# OpenBook_Schematic.net
KiCad netlist of a schematic drawn in EAGLE
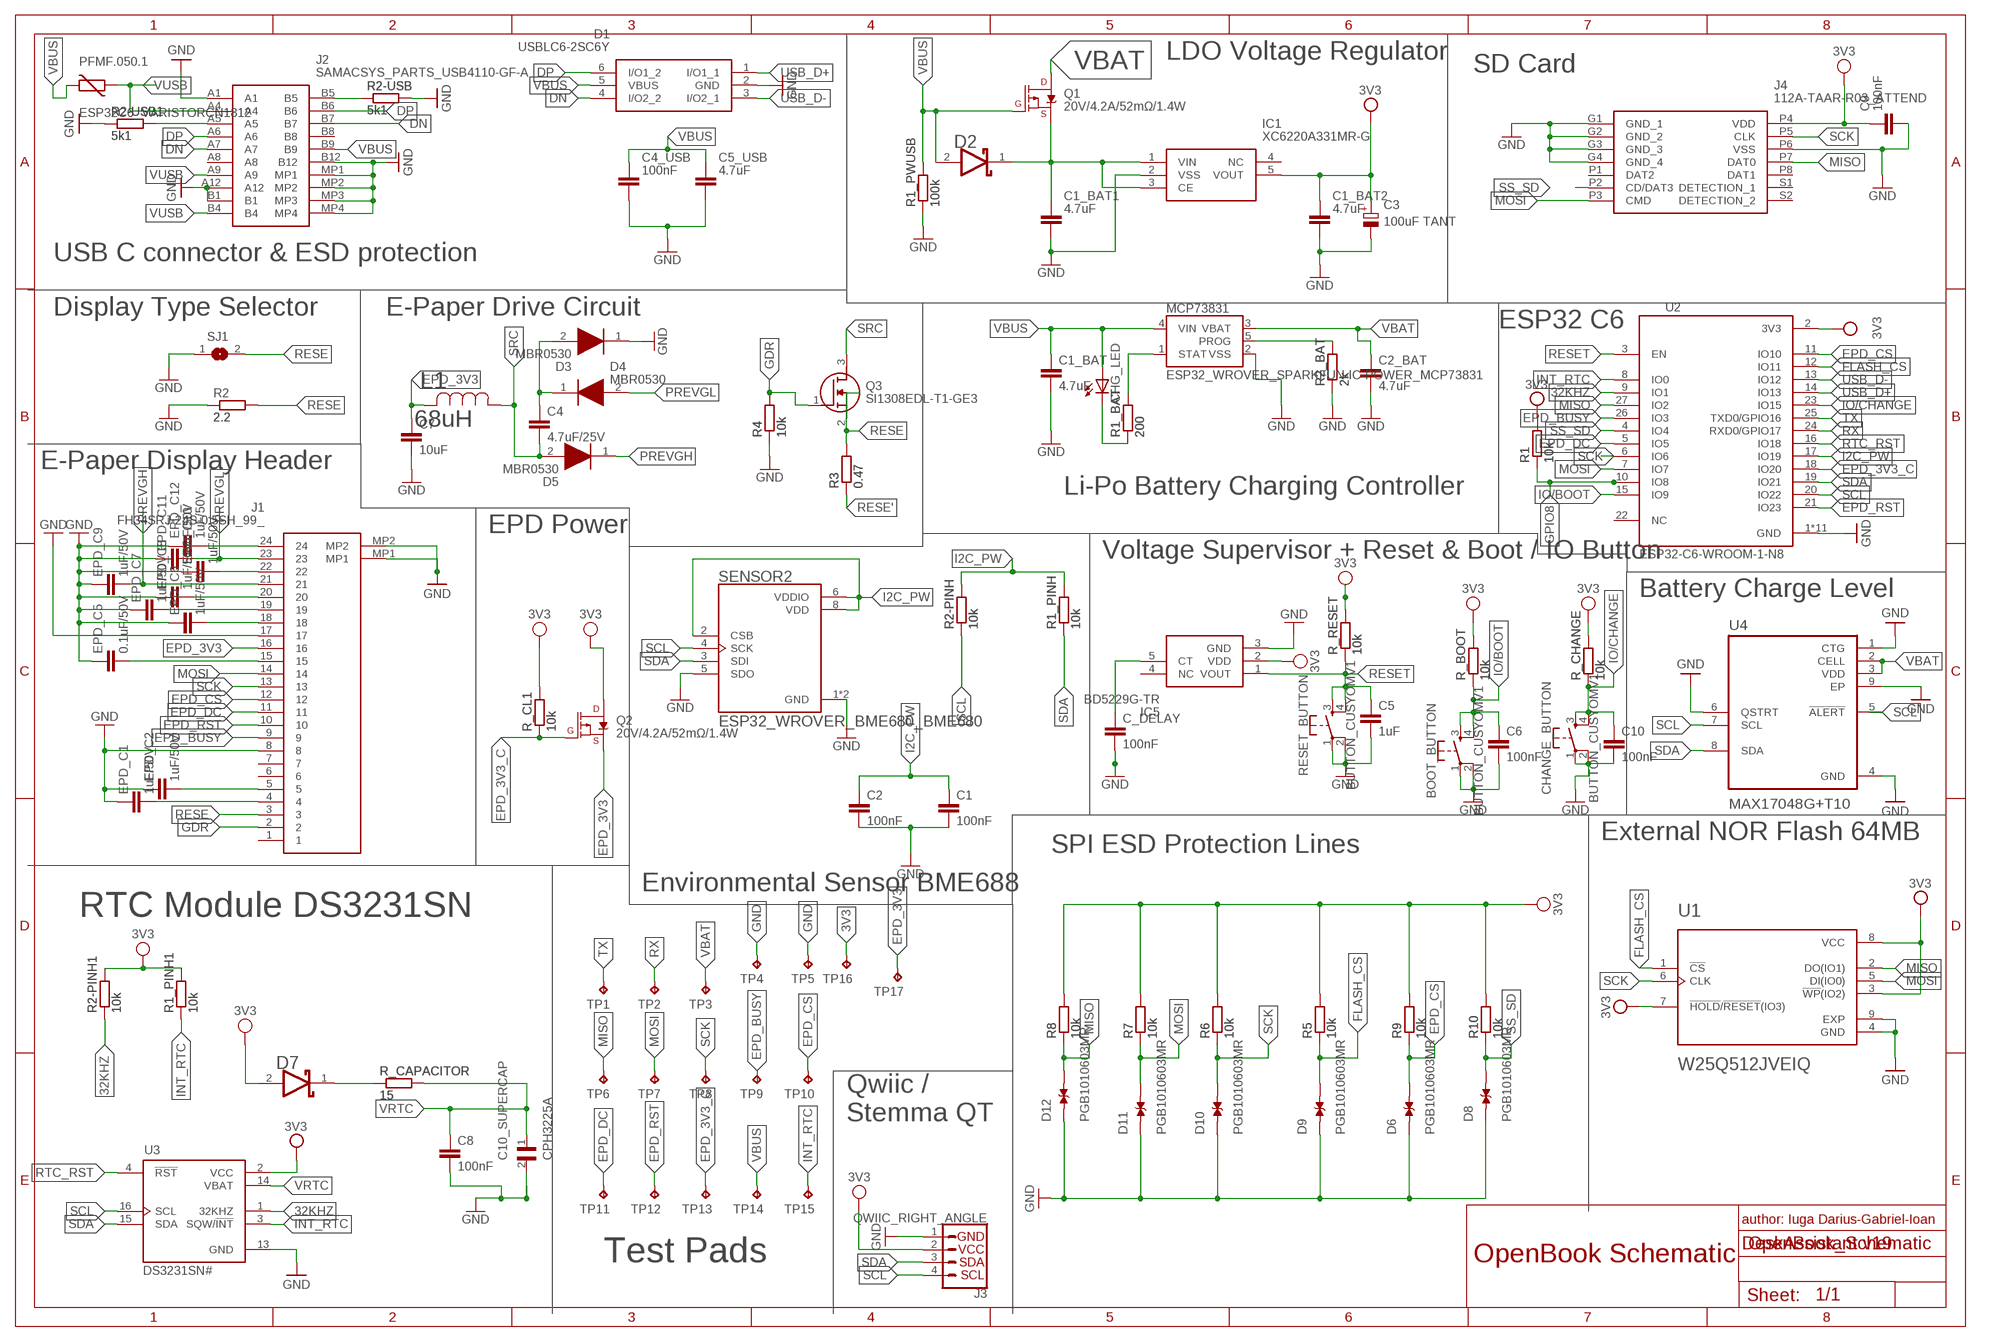
[diagram p0: schematic, sheet 1]

(export (version "E")
  (design (tool "Eeschema 10.0.6"))
  (components
    (comp (ref "BOOT_BUTTON")
      (value "BUTTON_CUSYOMV1")
      (footprint "eagle-import:MYBUTTON")
      (libsource (lib "eagle-import") (part "BUTTON_CUSYOMV1"))
    )
    (comp (ref "C1")
      (value "100nF")
      (footprint "eagle-import:ESP32_WROVER_EAGLE-LTSPICE_C0402")
      (libsource (lib "eagle-import") (part "ESP32_WROVER_EAGLE-LTSPICE_CC0402"))
    )
    (comp (ref "C1_BAT")
      (value "4.7uF")
      (footprint "eagle-import:ESP32_WROVER_EAGLE-LTSPICE_C0402")
      (libsource (lib "eagle-import") (part "ESP32_WROVER_EAGLE-LTSPICE_CC0402"))
    )
    (comp (ref "C1_BAT1")
      (value "4.7uF")
      (footprint "eagle-import:CAPC1005X60")
      (libsource (lib "eagle-import") (part "CCHIP-0402(1005-METRIC)_"))
    )
    (comp (ref "C1_BAT2")
      (value "4.7uF")
      (footprint "eagle-import:CAPM3216X180")
      (libsource (lib "eagle-import") (part "CTANTALUM-1206(3216-METRIC)_"))
    )
    (comp (ref "C2")
      (value "100nF")
      (footprint "eagle-import:ESP32_WROVER_EAGLE-LTSPICE_C0402")
      (libsource (lib "eagle-import") (part "ESP32_WROVER_EAGLE-LTSPICE_CC0402"))
    )
    (comp (ref "C2_BAT")
      (value "4.7uF")
      (footprint "eagle-import:ESP32_WROVER_EAGLE-LTSPICE_C0402")
      (libsource (lib "eagle-import") (part "ESP32_WROVER_EAGLE-LTSPICE_CC0402"))
    )
    (comp (ref "C3")
      (value "100uF TANT")
      (footprint "eagle-import:CAPMP3216X180N")
      (libsource (lib "eagle-import") (part "C-POLTANTALUM-1206(3216-METRIC)_"))
    )
    (comp (ref "C4")
      (value "4.7uF/25V")
      (footprint "eagle-import:EAGLE-LTSPICE_C0402")
      (libsource (lib "eagle-import") (part "EAGLE-LTSPICE_CC0402"))
    )
    (comp (ref "C4_USB")
      (value "100nF")
      (footprint "eagle-import:CAPC1005X60")
      (libsource (lib "eagle-import") (part "CCHIP-0402(1005-METRIC)_"))
    )
    (comp (ref "C5")
      (value "1uF")
      (footprint "eagle-import:ESP32_WROVER_EAGLE-LTSPICE_C0402")
      (libsource (lib "eagle-import") (part "ESP32_WROVER_EAGLE-LTSPICE_CC0402"))
    )
    (comp (ref "C5_USB")
      (value "4.7uF")
      (footprint "eagle-import:CAPC1005X60")
      (libsource (lib "eagle-import") (part "CCHIP-0402(1005-METRIC)_"))
    )
    (comp (ref "C6")
      (value "100nF")
      (footprint "eagle-import:ESP32_WROVER_EAGLE-LTSPICE_C0402")
      (libsource (lib "eagle-import") (part "ESP32_WROVER_EAGLE-LTSPICE_CC0402"))
    )
    (comp (ref "C7")
      (value "10uF")
      (footprint "eagle-import:EAGLE-LTSPICE_C0402")
      (libsource (lib "eagle-import") (part "EAGLE-LTSPICE_CC0402"))
    )
    (comp (ref "C8")
      (value "100nF")
      (footprint "eagle-import:EAGLE-LTSPICE_C0402")
      (libsource (lib "eagle-import") (part "EAGLE-LTSPICE_CC0402"))
    )
    (comp (ref "C9")
      (value "100nF")
      (footprint "eagle-import:CAPC1005X60")
      (libsource (lib "eagle-import") (part "CCHIP-0402(1005-METRIC)_"))
    )
    (comp (ref "C10")
      (value "100nF")
      (footprint "eagle-import:ESP32_WROVER_EAGLE-LTSPICE_C0402")
      (libsource (lib "eagle-import") (part "ESP32_WROVER_EAGLE-LTSPICE_CC0402"))
    )
    (comp (ref "C10_SUPERCAP")
      (value "CPH3225A")
      (footprint "eagle-import:CAPCP3225X100N")
      (fields (field (name "MF") "Seiko Instruments"))
      (libsource (lib "eagle-import") (part "CPH3225A"))
    )
    (comp (ref "CHANGE_BUTTON")
      (value "BUTTON_CUSYOMV1")
      (footprint "eagle-import:MYBUTTON")
      (libsource (lib "eagle-import") (part "BUTTON_CUSYOMV1"))
    )
    (comp (ref "CHG_LED")
      (value "ADAFRUIT_LEDCHIP-LED0603")
      (footprint "eagle-import:ADAFRUIT_CHIP-LED0603")
      (libsource (lib "eagle-import") (part "ADAFRUIT_LEDCHIP-LED0603"))
    )
    (comp (ref "C_DELAY")
      (value "100nF")
      (footprint "eagle-import:ESP32_WROVER_EAGLE-LTSPICE_C0402")
      (libsource (lib "eagle-import") (part "ESP32_WROVER_EAGLE-LTSPICE_CC0402"))
    )
    (comp (ref "D1")
      (value "USBLC6-2SC6Y")
      (footprint "eagle-import:SOT95P280X145-6N")
      (fields (field (name "MF") "STMicroelectronics"))
      (libsource (lib "eagle-import") (part "USBLC6-2SC6Y"))
    )
    (comp (ref "D2")
      (value "ESP32_WROVER_AVX---SD0805S020S1R0_AVX_SD0805S020S1R0_0_0AVX_SD0805S020S1R0_0_0")
      (footprint "eagle-import:ESP32_WROVER_AVX---SD0805S020S1R0_AVX_SD0805S020S1R0_0")
      (fields
        (field (name "DIGIKEY_PART_NUMBER") "478-7800-1-ND")
        (field (name "MF") "AVX")
        (field (name "MOUSER_PART_NUMBER") "581-SD0805S020S1R0")
      )
      (libsource (lib "eagle-import") (part "ESP32_WROVER_AVX---SD0805S020S1R0_AVX_SD0805S020S1R0_0_0AVX_SD0805S020S1R0_0_0"))
    )
    (comp (ref "D3")
      (value "MBR0530")
      (footprint "eagle-import:SOD3716X135N")
      (fields (field (name "MF") "ON Semiconductor"))
      (libsource (lib "eagle-import") (part "MBR0530"))
    )
    (comp (ref "D4")
      (value "MBR0530")
      (footprint "eagle-import:SOD3716X135N")
      (fields (field (name "MF") "ON Semiconductor"))
      (libsource (lib "eagle-import") (part "MBR0530"))
    )
    (comp (ref "D5")
      (value "MBR0530")
      (footprint "eagle-import:SOD3716X135N")
      (fields (field (name "MF") "ON Semiconductor"))
      (libsource (lib "eagle-import") (part "MBR0530"))
    )
    (comp (ref "D6")
      (value "PGB1010603MR")
      (footprint "eagle-import:DIOC1608X36N")
      (fields (field (name "MF") "Littelfuse Inc."))
      (libsource (lib "eagle-import") (part "PGB1010603MR"))
    )
    (comp (ref "D7")
      (value "ESP32_WROVER_AVX---SD0805S020S1R0_AVX_SD0805S020S1R0_0_0AVX_SD0805S020S1R0_0_0")
      (footprint "eagle-import:ESP32_WROVER_AVX---SD0805S020S1R0_AVX_SD0805S020S1R0_0")
      (fields
        (field (name "DIGIKEY_PART_NUMBER") "478-7800-1-ND")
        (field (name "MF") "AVX")
        (field (name "MOUSER_PART_NUMBER") "581-SD0805S020S1R0")
      )
      (libsource (lib "eagle-import") (part "ESP32_WROVER_AVX---SD0805S020S1R0_AVX_SD0805S020S1R0_0_0AVX_SD0805S020S1R0_0_0"))
    )
    (comp (ref "D8")
      (value "PGB1010603MR")
      (footprint "eagle-import:DIOC1608X36N")
      (fields (field (name "MF") "Littelfuse Inc."))
      (libsource (lib "eagle-import") (part "PGB1010603MR"))
    )
    (comp (ref "D9")
      (value "PGB1010603MR")
      (footprint "eagle-import:DIOC1608X36N")
      (fields (field (name "MF") "Littelfuse Inc."))
      (libsource (lib "eagle-import") (part "PGB1010603MR"))
    )
    (comp (ref "D10")
      (value "PGB1010603MR")
      (footprint "eagle-import:DIOC1608X36N")
      (fields (field (name "MF") "Littelfuse Inc."))
      (libsource (lib "eagle-import") (part "PGB1010603MR"))
    )
    (comp (ref "D11")
      (value "PGB1010603MR")
      (footprint "eagle-import:DIOC1608X36N")
      (fields (field (name "MF") "Littelfuse Inc."))
      (libsource (lib "eagle-import") (part "PGB1010603MR"))
    )
    (comp (ref "D12")
      (value "PGB1010603MR")
      (footprint "eagle-import:DIOC1608X36N")
      (fields (field (name "MF") "Littelfuse Inc."))
      (libsource (lib "eagle-import") (part "PGB1010603MR"))
    )
    (comp (ref "EPD_C1")
      (value "1uF/50V")
      (footprint "eagle-import:ESP32_WROVER_EAGLE-LTSPICE_C0402")
      (libsource (lib "eagle-import") (part "ESP32_WROVER_EAGLE-LTSPICE_CC0402"))
    )
    (comp (ref "EPD_C2")
      (value "1uF/50V")
      (footprint "eagle-import:ESP32_WROVER_EAGLE-LTSPICE_C0402")
      (libsource (lib "eagle-import") (part "ESP32_WROVER_EAGLE-LTSPICE_CC0402"))
    )
    (comp (ref "EPD_C5")
      (value "0.1uF/50V")
      (footprint "eagle-import:ESP32_WROVER_EAGLE-LTSPICE_C0402")
      (libsource (lib "eagle-import") (part "ESP32_WROVER_EAGLE-LTSPICE_CC0402"))
    )
    (comp (ref "EPD_C6")
      (value "1uF/50V")
      (footprint "eagle-import:ESP32_WROVER_EAGLE-LTSPICE_C0402")
      (libsource (lib "eagle-import") (part "ESP32_WROVER_EAGLE-LTSPICE_CC0402"))
    )
    (comp (ref "EPD_C7")
      (value "1uF/50V")
      (footprint "eagle-import:ESP32_WROVER_EAGLE-LTSPICE_C0402")
      (libsource (lib "eagle-import") (part "ESP32_WROVER_EAGLE-LTSPICE_CC0402"))
    )
    (comp (ref "EPD_C8")
      (value "1uF/50V")
      (footprint "eagle-import:ESP32_WROVER_EAGLE-LTSPICE_C0402")
      (libsource (lib "eagle-import") (part "ESP32_WROVER_EAGLE-LTSPICE_CC0402"))
    )
    (comp (ref "EPD_C9")
      (value "1uF/50V")
      (footprint "eagle-import:ESP32_WROVER_EAGLE-LTSPICE_C0402")
      (libsource (lib "eagle-import") (part "ESP32_WROVER_EAGLE-LTSPICE_CC0402"))
    )
    (comp (ref "EPD_C10")
      (value "1uF/50V")
      (footprint "eagle-import:ESP32_WROVER_EAGLE-LTSPICE_C0402")
      (libsource (lib "eagle-import") (part "ESP32_WROVER_EAGLE-LTSPICE_CC0402"))
    )
    (comp (ref "EPD_C11")
      (value "1uF/50V")
      (footprint "eagle-import:ESP32_WROVER_EAGLE-LTSPICE_C0402")
      (libsource (lib "eagle-import") (part "ESP32_WROVER_EAGLE-LTSPICE_CC0402"))
    )
    (comp (ref "EPD_C12")
      (value "1uF/50V")
      (footprint "eagle-import:ESP32_WROVER_EAGLE-LTSPICE_C0402")
      (libsource (lib "eagle-import") (part "ESP32_WROVER_EAGLE-LTSPICE_CC0402"))
    )
    (comp (ref "IC1")
      (value "XC6220A331MR-G")
      (footprint "eagle-import:SOT95P280X120-5N")
      (fields (field (name "MOUSER_PART_NUMBER") "865-XC6220A331MR-G"))
      (libsource (lib "eagle-import") (part "XC6220A331MR-G"))
    )
    (comp (ref "IC5")
      (value "BD5229G-TR")
      (footprint "eagle-import:SOT95P280X125-5N")
      (fields (field (name "MOUSER_PART_NUMBER") "755-BD5229G-TR"))
      (libsource (lib "eagle-import") (part "BD5229G-TR"))
    )
    (comp (ref "J1")
      (value "FH34SRJ-24S-0.5SH_99_")
      (footprint "eagle-import:FH34SRJ24S05SH99")
      (fields
        (field (name "MANUFACTURER_PART_NUMBER") "FH34SRJ-24S-0.5SH(99)")
        (field (name "MOUSER_PART_NUMBER") "798-FH34SRJ24S05SH99")
      )
      (libsource (lib "eagle-import") (part "FH34SRJ-24S-0.5SH_99_"))
    )
    (comp (ref "J2")
      (value "SAMACSYS_PARTS_USB4110-GF-A")
      (footprint "eagle-import:SAMACSYS_PARTS_USB4110GFA")
      (fields
        (field (name "MANUFACTURER_PART_NUMBER") "USB4110-GF-A")
        (field (name "MOUSER_PART_NUMBER") "640-USB4110-GF-A")
      )
      (libsource (lib "eagle-import") (part "SAMACSYS_PARTS_USB4110-GF-A"))
    )
    (comp (ref "J3")
      (value "QWIIC_RIGHT_ANGLE")
      (footprint "eagle-import:JST04_1MM_RA")
      (libsource (lib "eagle-import") (part "QWIIC_CONNECTORJS-1MM"))
    )
    (comp (ref "J4")
      (value "112A-TAAR-R03_ATTEND")
      (footprint "eagle-import:112ATAARR03ATTEND")
      (fields (field (name "MANUFACTURER_PART_NUMBER") "112A-TAAR-R03 ATTEND"))
      (libsource (lib "eagle-import") (part "112A-TAAR-R03_ATTEND"))
    )
    (comp (ref "L1")
      (value "68uH")
      (footprint "eagle-import:IND_4828-WE-TPC_WRE")
      (fields
        (field (name "MANUFACTURER_PART_NUMBER") "744043680")
        (field (name "COPYRIGHT") "Copyright (C) 2024 Ultra Librarian. All rights reserved.")
      )
      (libsource (lib "eagle-import") (part "744043680IND_4828-WE-TPC_WRE"))
    )
    (comp (ref "MCP73831")
      (value "ESP32_WROVER_SPARKFUN-IC-POWER_MCP73831")
      (footprint "eagle-import:ESP32_WROVER_SPARKFUN-IC-POWER_SOT23-5")
      (libsource (lib "eagle-import") (part "ESP32_WROVER_SPARKFUN-IC-POWER_MCP73831"))
    )
    (comp (ref "PFMF.050.1")
      (value "ESP32C6_VARISTORCN1812")
      (footprint "eagle-import:ESP32C6_VARISTOR_CT_CN1812")
      (libsource (lib "eagle-import") (part "ESP32C6_VARISTORCN1812"))
    )
    (comp (ref "Q1")
      (value "20V/4.2A/52mΩ/1.4W")
      (footprint "eagle-import:ESP32_WROVER_SPARKFUN-DISCRETESEMI_SOT23-3")
      (libsource (lib "eagle-import") (part "ESP32_WROVER_SPARKFUN-DISCRETESEMI_MOSFET_PCH-DMG2305UX-7"))
    )
    (comp (ref "Q2")
      (value "20V/4.2A/52mΩ/1.4W")
      (footprint "eagle-import:ESP32_WROVER_SPARKFUN-DISCRETESEMI_SOT23-3")
      (libsource (lib "eagle-import") (part "ESP32_WROVER_SPARKFUN-DISCRETESEMI_MOSFET_PCH-DMG2305UX-7"))
    )
    (comp (ref "Q3")
      (value "SI1308EDL-T1-GE3")
      (footprint "eagle-import:SOT65P210X110-3N")
      (fields
        (field (name "MANUFACTURER_PART_NUMBER") "Si1308EDL-T1-GE3")
        (field (name "MOUSER_PART_NUMBER") "78-SI1308EDL-T1-GE3")
      )
      (libsource (lib "eagle-import") (part "SI1308EDL-T1-GE3"))
    )
    (comp (ref "R1")
      (value "10k")
      (footprint "eagle-import:ESP32_WROVER_EAGLE-LTSPICE_R0402")
      (libsource (lib "eagle-import") (part "ESP32_WROVER_EAGLE-LTSPICE_RR0402"))
    )
    (comp (ref "R1_BAT")
      (value "200")
      (footprint "eagle-import:ESP32_WROVER_EAGLE-LTSPICE_R0402")
      (libsource (lib "eagle-import") (part "ESP32_WROVER_EAGLE-LTSPICE_RR0402"))
    )
    (comp (ref "R1_PINH")
      (value "10k")
      (footprint "eagle-import:ESP32_WROVER_EAGLE-LTSPICE_R0402")
      (libsource (lib "eagle-import") (part "ESP32_WROVER_EAGLE-LTSPICE_RR0402"))
    )
    (comp (ref "R1_PINH1")
      (value "10k")
      (footprint "eagle-import:ESP32_WROVER_EAGLE-LTSPICE_R0402")
      (libsource (lib "eagle-import") (part "ESP32_WROVER_EAGLE-LTSPICE_RR0402"))
    )
    (comp (ref "R1_PWUSB")
      (value "100k")
      (footprint "eagle-import:ESP32_WROVER_EAGLE-LTSPICE_R0402")
      (libsource (lib "eagle-import") (part "ESP32_WROVER_EAGLE-LTSPICE_RR0402"))
    )
    (comp (ref "R2")
      (value "2.2")
      (footprint "eagle-import:ESP32_WROVER_EAGLE-LTSPICE_R0402")
      (libsource (lib "eagle-import") (part "ESP32_WROVER_EAGLE-LTSPICE_RR0402"))
    )
    (comp (ref "R2-PINH")
      (value "10k")
      (footprint "eagle-import:ESP32_WROVER_EAGLE-LTSPICE_R0402")
      (libsource (lib "eagle-import") (part "ESP32_WROVER_EAGLE-LTSPICE_RR0402"))
    )
    (comp (ref "R2-PINH1")
      (value "10k")
      (footprint "eagle-import:ESP32_WROVER_EAGLE-LTSPICE_R0402")
      (libsource (lib "eagle-import") (part "ESP32_WROVER_EAGLE-LTSPICE_RR0402"))
    )
    (comp (ref "R2-USB")
      (value "5k1")
      (footprint "eagle-import:ESP32_WROVER_EAGLE-LTSPICE_R0402")
      (libsource (lib "eagle-import") (part "ESP32_WROVER_EAGLE-LTSPICE_RR0402"))
    )
    (comp (ref "R2-USB1")
      (value "5k1")
      (footprint "eagle-import:ESP32_WROVER_EAGLE-LTSPICE_R0402")
      (libsource (lib "eagle-import") (part "ESP32_WROVER_EAGLE-LTSPICE_RR0402"))
    )
    (comp (ref "R2_BAT")
      (value "2k")
      (footprint "eagle-import:ESP32_WROVER_EAGLE-LTSPICE_R0402")
      (libsource (lib "eagle-import") (part "ESP32_WROVER_EAGLE-LTSPICE_RR0402"))
    )
    (comp (ref "R3")
      (value "0.47")
      (footprint "eagle-import:ESP32_WROVER_EAGLE-LTSPICE_R0402")
      (libsource (lib "eagle-import") (part "ESP32_WROVER_EAGLE-LTSPICE_RR0402"))
    )
    (comp (ref "R4")
      (value "10k")
      (footprint "eagle-import:ESP32_WROVER_EAGLE-LTSPICE_R0402")
      (libsource (lib "eagle-import") (part "ESP32_WROVER_EAGLE-LTSPICE_RR0402"))
    )
    (comp (ref "R5")
      (value "10k")
      (footprint "eagle-import:ESP32_WROVER_EAGLE-LTSPICE_R0402")
      (libsource (lib "eagle-import") (part "ESP32_WROVER_EAGLE-LTSPICE_RR0402"))
    )
    (comp (ref "R6")
      (value "10k")
      (footprint "eagle-import:ESP32_WROVER_EAGLE-LTSPICE_R0402")
      (libsource (lib "eagle-import") (part "ESP32_WROVER_EAGLE-LTSPICE_RR0402"))
    )
    (comp (ref "R7")
      (value "10k")
      (footprint "eagle-import:ESP32_WROVER_EAGLE-LTSPICE_R0402")
      (libsource (lib "eagle-import") (part "ESP32_WROVER_EAGLE-LTSPICE_RR0402"))
    )
    (comp (ref "R8")
      (value "10k")
      (footprint "eagle-import:ESP32_WROVER_EAGLE-LTSPICE_R0402")
      (libsource (lib "eagle-import") (part "ESP32_WROVER_EAGLE-LTSPICE_RR0402"))
    )
    (comp (ref "R9")
      (value "10k")
      (footprint "eagle-import:ESP32_WROVER_EAGLE-LTSPICE_R0402")
      (libsource (lib "eagle-import") (part "ESP32_WROVER_EAGLE-LTSPICE_RR0402"))
    )
    (comp (ref "R10")
      (value "10k")
      (footprint "eagle-import:ESP32_WROVER_EAGLE-LTSPICE_R0402")
      (libsource (lib "eagle-import") (part "ESP32_WROVER_EAGLE-LTSPICE_RR0402"))
    )
    (comp (ref "RESET_BUTTON")
      (value "BUTTON_CUSYOMV1")
      (footprint "eagle-import:MYBUTTON")
      (libsource (lib "eagle-import") (part "BUTTON_CUSYOMV1"))
    )
    (comp (ref "R_BOOT")
      (value "10k")
      (footprint "eagle-import:ESP32_WROVER_EAGLE-LTSPICE_R0402")
      (libsource (lib "eagle-import") (part "ESP32_WROVER_EAGLE-LTSPICE_RR0402"))
    )
    (comp (ref "R_CAPACITOR")
      (value "15")
      (footprint "eagle-import:ESP32_WROVER_EAGLE-LTSPICE_R0402")
      (libsource (lib "eagle-import") (part "ESP32_WROVER_EAGLE-LTSPICE_RR0402"))
    )
    (comp (ref "R_CHANGE")
      (value "10k")
      (footprint "eagle-import:ESP32_WROVER_EAGLE-LTSPICE_R0402")
      (libsource (lib "eagle-import") (part "ESP32_WROVER_EAGLE-LTSPICE_RR0402"))
    )
    (comp (ref "R_CL1")
      (value "10k")
      (footprint "eagle-import:ESP32_WROVER_EAGLE-LTSPICE_R0402")
      (libsource (lib "eagle-import") (part "ESP32_WROVER_EAGLE-LTSPICE_RR0402"))
    )
    (comp (ref "R_RESET")
      (value "10k")
      (footprint "eagle-import:ESP32_WROVER_EAGLE-LTSPICE_R0402")
      (libsource (lib "eagle-import") (part "ESP32_WROVER_EAGLE-LTSPICE_RR0402"))
    )
    (comp (ref "SENSOR2")
      (value "ESP32_WROVER_BME680_BME680")
      (footprint "eagle-import:ESP32_WROVER_BME680_PSON80P300X300X100-8N")
      (fields (field (name "MF") "Bosch Sensortec") (field (name "MP") "BME680"))
      (libsource (lib "eagle-import") (part "ESP32_WROVER_BME680_BME680"))
    )
    (comp (ref "SJ1") (value "SJ") (footprint "eagle-import:SJ") (libsource (lib "eagle-import") (part "SJ")))
    (comp (ref "TP1")
      (value "TPB1,27")
      (footprint "eagle-import:B1,27")
      (libsource (lib "eagle-import") (part "TPB1,27"))
    )
    (comp (ref "TP2")
      (value "TPB1,27")
      (footprint "eagle-import:B1,27")
      (libsource (lib "eagle-import") (part "TPB1,27"))
    )
    (comp (ref "TP3")
      (value "TPB1,27")
      (footprint "eagle-import:B1,27")
      (libsource (lib "eagle-import") (part "TPB1,27"))
    )
    (comp (ref "TP4")
      (value "TPB1,27")
      (footprint "eagle-import:B1,27")
      (libsource (lib "eagle-import") (part "TPB1,27"))
    )
    (comp (ref "TP5")
      (value "TPB1,27")
      (footprint "eagle-import:B1,27")
      (libsource (lib "eagle-import") (part "TPB1,27"))
    )
    (comp (ref "TP6")
      (value "TPB1,27")
      (footprint "eagle-import:B1,27")
      (libsource (lib "eagle-import") (part "TPB1,27"))
    )
    (comp (ref "TP7")
      (value "TPB1,27")
      (footprint "eagle-import:B1,27")
      (libsource (lib "eagle-import") (part "TPB1,27"))
    )
    (comp (ref "TP8")
      (value "TPB1,27")
      (footprint "eagle-import:B1,27")
      (libsource (lib "eagle-import") (part "TPB1,27"))
    )
    (comp (ref "TP9")
      (value "TPB1,27")
      (footprint "eagle-import:B1,27")
      (libsource (lib "eagle-import") (part "TPB1,27"))
    )
    (comp (ref "TP10")
      (value "TPB1,27")
      (footprint "eagle-import:B1,27")
      (libsource (lib "eagle-import") (part "TPB1,27"))
    )
    (comp (ref "TP11")
      (value "TPB1,27")
      (footprint "eagle-import:B1,27")
      (libsource (lib "eagle-import") (part "TPB1,27"))
    )
    (comp (ref "TP12")
      (value "TPB1,27")
      (footprint "eagle-import:B1,27")
      (libsource (lib "eagle-import") (part "TPB1,27"))
    )
    (comp (ref "TP13")
      (value "TPB1,27")
      (footprint "eagle-import:B1,27")
      (libsource (lib "eagle-import") (part "TPB1,27"))
    )
    (comp (ref "TP14")
      (value "TPB1,27")
      (footprint "eagle-import:B1,27")
      (libsource (lib "eagle-import") (part "TPB1,27"))
    )
    (comp (ref "TP15")
      (value "TPB1,27")
      (footprint "eagle-import:B1,27")
      (libsource (lib "eagle-import") (part "TPB1,27"))
    )
    (comp (ref "TP16")
      (value "TPB1,27")
      (footprint "eagle-import:B1,27")
      (libsource (lib "eagle-import") (part "TPB1,27"))
    )
    (comp (ref "TP17")
      (value "TPB1,27")
      (footprint "eagle-import:B1,27")
      (libsource (lib "eagle-import") (part "TPB1,27"))
    )
    (comp (ref "U1")
      (value "W25Q512JVEIQ")
      (footprint "eagle-import:SON127P600X800X80-9N")
      (fields (field (name "MF") "Winbond Electronics"))
      (libsource (lib "eagle-import") (part "W25Q512JVEIQ"))
    )
    (comp (ref "U2")
      (value "ESP32-C6-WROOM-1-N8")
      (footprint "eagle-import:XCVR_ESP32-C6-WROOM-1-N8")
      (fields (field (name "MF") "Espressif Systems"))
      (libsource (lib "eagle-import") (part "ESP32-C6-WROOM-1-N8"))
    )
    (comp (ref "U3")
      (value "DS3231SN#")
      (footprint "eagle-import:SOIC127P1032X265-16N")
      (fields (field (name "MF") "Analog Devices"))
      (libsource (lib "eagle-import") (part "DS3231SN#"))
    )
    (comp (ref "U4")
      (value "MAX17048G+T10")
      (footprint "eagle-import:SON50P200X200X80-9N")
      (fields (field (name "MF") "Analog Devices"))
      (libsource (lib "eagle-import") (part "MAX17048G+T10"))
    )
  )
  (nets
    (net (code "1") (name "3V3") (class "Default")
      (node (ref "C1_BAT2") (pin "1") (pinfunction "1_1") (pintype "passive"))
      (node (ref "C3") (pin "1") (pinfunction "+_1") (pintype "passive"))
      (node (ref "C9") (pin "1") (pinfunction "1_1") (pintype "passive"))
      (node (ref "D7") (pin "2") (pinfunction "ANODE_2") (pintype "bidirectional"))
      (node (ref "IC1") (pin "5") (pinfunction "VOUT_5") (pintype "bidirectional"))
      (node (ref "IC5") (pin "2") (pinfunction "VDD_2") (pintype "bidirectional"))
      (node (ref "J3") (pin "2") (pinfunction "2_2") (pintype "power_in"))
      (node (ref "J4") (pin "P4") (pinfunction "VDD_P4") (pintype "bidirectional"))
      (node (ref "Q2") (pin "3") (pinfunction "D_3") (pintype "bidirectional"))
      (node (ref "R1") (pin "2") (pinfunction "2_2") (pintype "passive"))
      (node (ref "R10") (pin "2") (pinfunction "2_2") (pintype "passive"))
      (node (ref "R1_PINH1") (pin "2") (pinfunction "2_2") (pintype "passive"))
      (node (ref "R2-PINH1") (pin "2") (pinfunction "2_2") (pintype "passive"))
      (node (ref "R5") (pin "2") (pinfunction "2_2") (pintype "passive"))
      (node (ref "R6") (pin "2") (pinfunction "2_2") (pintype "passive"))
      (node (ref "R7") (pin "2") (pinfunction "2_2") (pintype "passive"))
      (node (ref "R8") (pin "2") (pinfunction "2_2") (pintype "passive"))
      (node (ref "R9") (pin "2") (pinfunction "2_2") (pintype "passive"))
      (node (ref "R_BOOT") (pin "2") (pinfunction "2_2") (pintype "passive"))
      (node (ref "R_CHANGE") (pin "2") (pinfunction "2_2") (pintype "passive"))
      (node (ref "R_CL1") (pin "2") (pinfunction "2_2") (pintype "passive"))
      (node (ref "R_RESET") (pin "2") (pinfunction "2_2") (pintype "passive"))
      (node (ref "TP16") (pin "TP") (pinfunction "TP_TP") (pintype "input"))
      (node (ref "U1") (pin "3") (pinfunction "~{WP}(IO2)_3") (pintype "bidirectional"))
      (node (ref "U1") (pin "7") (pinfunction "~{HOLD}/~{RESET}(IO3)_7") (pintype "bidirectional"))
      (node (ref "U1") (pin "8") (pinfunction "VCC_8") (pintype "power_in"))
      (node (ref "U2") (pin "2") (pinfunction "3V3_2") (pintype "power_in"))
      (node (ref "U3") (pin "2") (pinfunction "VCC_2") (pintype "power_in"))
    )
    (net (code "2") (name "32KHZ") (class "Default")
      (node (ref "R2-PINH1") (pin "1") (pinfunction "1_1") (pintype "passive"))
      (node (ref "U2") (pin "9") (pinfunction "IO1_9") (pintype "bidirectional"))
      (node (ref "U3") (pin "1") (pinfunction "32KHZ_1") (pintype "output"))
    )
    (net (code "3") (name "DN") (class "Default")
      (node (ref "D1") (pin "4") (pinfunction "I/O2_2_4") (pintype "bidirectional"))
      (node (ref "J2") (pin "A7") (pinfunction "A7_A7") (pintype "bidirectional"))
      (node (ref "J2") (pin "B7") (pinfunction "B7_B7") (pintype "bidirectional"))
    )
    (net (code "4") (name "DP") (class "Default")
      (node (ref "D1") (pin "6") (pinfunction "I/O1_2_6") (pintype "bidirectional"))
      (node (ref "J2") (pin "A6") (pinfunction "A6_A6") (pintype "bidirectional"))
      (node (ref "J2") (pin "B6") (pinfunction "B6_B6") (pintype "bidirectional"))
    )
    (net (code "5") (name "EPD_3V3") (class "Default")
      (node (ref "C7") (pin "1") (pinfunction "1_1") (pintype "passive"))
      (node (ref "J1") (pin "16") (pinfunction "16_16") (pintype "bidirectional"))
      (node (ref "L1") (pin "2") (pinfunction "2_2") (pintype "passive"))
      (node (ref "Q2") (pin "2") (pinfunction "S_2") (pintype "bidirectional"))
      (node (ref "TP17") (pin "TP") (pinfunction "TP_TP") (pintype "input"))
    )
    (net (code "6") (name "EPD_3V3_C") (class "Default")
      (node (ref "Q2") (pin "1") (pinfunction "G_1") (pintype "bidirectional"))
      (node (ref "R_CL1") (pin "1") (pinfunction "1_1") (pintype "passive"))
      (node (ref "TP13") (pin "TP") (pinfunction "TP_TP") (pintype "input"))
      (node (ref "U2") (pin "18") (pinfunction "IO20_18") (pintype "bidirectional"))
    )
    (net (code "7") (name "EPD_BUSY") (class "Default")
      (node (ref "J1") (pin "9") (pinfunction "9_9") (pintype "bidirectional"))
      (node (ref "TP9") (pin "TP") (pinfunction "TP_TP") (pintype "input"))
      (node (ref "U2") (pin "26") (pinfunction "IO3_26") (pintype "bidirectional"))
    )
    (net (code "8") (name "EPD_CS") (class "Default")
      (node (ref "D6") (pin "2") (pinfunction "2_2") (pintype "passive"))
      (node (ref "J1") (pin "12") (pinfunction "12_12") (pintype "bidirectional"))
      (node (ref "R9") (pin "1") (pinfunction "1_1") (pintype "passive"))
      (node (ref "TP10") (pin "TP") (pinfunction "TP_TP") (pintype "input"))
      (node (ref "U2") (pin "11") (pinfunction "IO10_11") (pintype "bidirectional"))
    )
    (net (code "9") (name "EPD_DC") (class "Default")
      (node (ref "J1") (pin "11") (pinfunction "11_11") (pintype "bidirectional"))
      (node (ref "TP11") (pin "TP") (pinfunction "TP_TP") (pintype "input"))
      (node (ref "U2") (pin "5") (pinfunction "IO5_5") (pintype "bidirectional"))
    )
    (net (code "10") (name "EPD_RST") (class "Default")
      (node (ref "J1") (pin "10") (pinfunction "10_10") (pintype "bidirectional"))
      (node (ref "TP12") (pin "TP") (pinfunction "TP_TP") (pintype "input"))
      (node (ref "U2") (pin "21") (pinfunction "IO23_21") (pintype "bidirectional"))
    )
    (net (code "11") (name "FLASH_CS") (class "Default")
      (node (ref "D9") (pin "2") (pinfunction "2_2") (pintype "passive"))
      (node (ref "R5") (pin "1") (pinfunction "1_1") (pintype "passive"))
      (node (ref "U1") (pin "1") (pinfunction "~{CS}_1") (pintype "input"))
      (node (ref "U2") (pin "12") (pinfunction "IO11_12") (pintype "bidirectional"))
    )
    (net (code "12") (name "GDR") (class "Default")
      (node (ref "J1") (pin "2") (pinfunction "2_2") (pintype "bidirectional"))
      (node (ref "Q3") (pin "1") (pinfunction "G_1") (pintype "bidirectional"))
      (node (ref "R4") (pin "2") (pinfunction "2_2") (pintype "passive"))
    )
    (net (code "13") (name "GND") (class "Default")
      (node (ref "BOOT_BUTTON") (pin "1") (pinfunction "1_1") (pintype "passive"))
      (node (ref "BOOT_BUTTON") (pin "2") (pinfunction "2_2") (pintype "passive"))
      (node (ref "C1") (pin "2") (pinfunction "2_2") (pintype "passive"))
      (node (ref "C10") (pin "2") (pinfunction "2_2") (pintype "passive"))
      (node (ref "C10_SUPERCAP") (pin "2") (pinfunction "2_2") (pintype "passive"))
      (node (ref "C1_BAT") (pin "2") (pinfunction "2_2") (pintype "passive"))
      (node (ref "C1_BAT1") (pin "2") (pinfunction "2_2") (pintype "passive"))
      (node (ref "C1_BAT2") (pin "2") (pinfunction "2_2") (pintype "passive"))
      (node (ref "C2") (pin "2") (pinfunction "2_2") (pintype "passive"))
      (node (ref "C2_BAT") (pin "2") (pinfunction "2_2") (pintype "passive"))
      (node (ref "C3") (pin "2") (pinfunction "-_2") (pintype "passive"))
      (node (ref "C4_USB") (pin "2") (pinfunction "2_2") (pintype "passive"))
      (node (ref "C5") (pin "2") (pinfunction "2_2") (pintype "passive"))
      (node (ref "C5_USB") (pin "2") (pinfunction "2_2") (pintype "passive"))
      (node (ref "C6") (pin "2") (pinfunction "2_2") (pintype "passive"))
      (node (ref "C7") (pin "2") (pinfunction "2_2") (pintype "passive"))
      (node (ref "C8") (pin "2") (pinfunction "2_2") (pintype "passive"))
      (node (ref "C9") (pin "2") (pinfunction "2_2") (pintype "passive"))
      (node (ref "CHANGE_BUTTON") (pin "1") (pinfunction "1_1") (pintype "passive"))
      (node (ref "CHANGE_BUTTON") (pin "2") (pinfunction "2_2") (pintype "passive"))
      (node (ref "C_DELAY") (pin "2") (pinfunction "2_2") (pintype "passive"))
      (node (ref "D1") (pin "2") (pinfunction "GND_2") (pintype "bidirectional"))
      (node (ref "D10") (pin "1") (pinfunction "1_1") (pintype "passive"))
      (node (ref "D11") (pin "1") (pinfunction "1_1") (pintype "passive"))
      (node (ref "D12") (pin "1") (pinfunction "1_1") (pintype "passive"))
      (node (ref "D3") (pin "1") (pinfunction "K_1") (pintype "bidirectional"))
      (node (ref "D6") (pin "1") (pinfunction "1_1") (pintype "passive"))
      (node (ref "D8") (pin "1") (pinfunction "1_1") (pintype "passive"))
      (node (ref "D9") (pin "1") (pinfunction "1_1") (pintype "passive"))
      (node (ref "EPD_C1") (pin "1") (pinfunction "1_1") (pintype "passive"))
      (node (ref "EPD_C10") (pin "1") (pinfunction "1_1") (pintype "passive"))
      (node (ref "EPD_C11") (pin "1") (pinfunction "1_1") (pintype "passive"))
      (node (ref "EPD_C12") (pin "1") (pinfunction "1_1") (pintype "passive"))
      (node (ref "EPD_C2") (pin "1") (pinfunction "1_1") (pintype "passive"))
      (node (ref "EPD_C5") (pin "1") (pinfunction "1_1") (pintype "passive"))
      (node (ref "EPD_C6") (pin "1") (pinfunction "1_1") (pintype "passive"))
      (node (ref "EPD_C7") (pin "1") (pinfunction "1_1") (pintype "passive"))
      (node (ref "EPD_C8") (pin "1") (pinfunction "1_1") (pintype "passive"))
      (node (ref "EPD_C9") (pin "1") (pinfunction "1_1") (pintype "passive"))
      (node (ref "IC1") (pin "2") (pinfunction "VSS_2") (pintype "bidirectional"))
      (node (ref "IC5") (pin "3") (pinfunction "GND_3") (pintype "bidirectional"))
      (node (ref "J1") (pin "17") (pinfunction "17_17") (pintype "bidirectional"))
      (node (ref "J1") (pin "8") (pinfunction "8_8") (pintype "bidirectional"))
      (node (ref "J1") (pin "MP1") (pinfunction "MP1_MP1") (pintype "bidirectional"))
      (node (ref "J1") (pin "MP2") (pinfunction "MP2_MP2") (pintype "bidirectional"))
      (node (ref "J2") (pin "A1") (pinfunction "A1_A1") (pintype "bidirectional"))
      (node (ref "J2") (pin "A12") (pinfunction "A12_A12") (pintype "bidirectional"))
      (node (ref "J2") (pin "B1") (pinfunction "B1_B1") (pintype "bidirectional"))
      (node (ref "J2") (pin "B12") (pinfunction "B12_B12") (pintype "bidirectional"))
      (node (ref "J2") (pin "MP1") (pinfunction "MP1_MP1") (pintype "bidirectional"))
      (node (ref "J2") (pin "MP2") (pinfunction "MP2_MP2") (pintype "bidirectional"))
      (node (ref "J2") (pin "MP3") (pinfunction "MP3_MP3") (pintype "bidirectional"))
      (node (ref "J2") (pin "MP4") (pinfunction "MP4_MP4") (pintype "bidirectional"))
      (node (ref "J3") (pin "1") (pinfunction "1_1") (pintype "power_in"))
      (node (ref "J4") (pin "G1") (pinfunction "GND_1_G1") (pintype "bidirectional"))
      (node (ref "J4") (pin "G2") (pinfunction "GND_2_G2") (pintype "bidirectional"))
      (node (ref "J4") (pin "G3") (pinfunction "GND_3_G3") (pintype "bidirectional"))
      (node (ref "J4") (pin "G4") (pinfunction "GND_4_G4") (pintype "bidirectional"))
      (node (ref "J4") (pin "P6") (pinfunction "VSS_P6") (pintype "bidirectional"))
      (node (ref "MCP73831") (pin "2") (pinfunction "VSS_2") (pintype "power_in"))
      (node (ref "R1_PWUSB") (pin "1") (pinfunction "1_1") (pintype "passive"))
      (node (ref "R2") (pin "1") (pinfunction "1_1") (pintype "passive"))
      (node (ref "R2-USB") (pin "2") (pinfunction "2_2") (pintype "passive"))
      (node (ref "R2-USB1") (pin "1") (pinfunction "1_1") (pintype "passive"))
      (node (ref "R2_BAT") (pin "1") (pinfunction "1_1") (pintype "passive"))
      (node (ref "R4") (pin "1") (pinfunction "1_1") (pintype "passive"))
      (node (ref "RESET_BUTTON") (pin "1") (pinfunction "1_1") (pintype "passive"))
      (node (ref "RESET_BUTTON") (pin "2") (pinfunction "2_2") (pintype "passive"))
      (node (ref "SENSOR2") (pin "1") (pinfunction "GND_1") (pintype "power_in"))
      (node (ref "SENSOR2") (pin "5") (pinfunction "SDO_5") (pintype "bidirectional"))
      (node (ref "SENSOR2") (pin "7") (pinfunction "GND_7") (pintype "power_in"))
      (node (ref "SJ1") (pin "1") (pinfunction "1_1") (pintype "passive"))
      (node (ref "TP4") (pin "TP") (pinfunction "TP_TP") (pintype "input"))
      (node (ref "TP5") (pin "TP") (pinfunction "TP_TP") (pintype "input"))
      (node (ref "U1") (pin "4") (pinfunction "GND_4") (pintype "power_in"))
      (node (ref "U1") (pin "9") (pinfunction "EXP_9") (pintype "passive"))
      (node (ref "U2") (pin "1") (pinfunction "GND_1") (pintype "power_in"))
      (node (ref "U2") (pin "28") (pinfunction "GND_28") (pintype "power_in"))
      (node (ref "U2") (pin "29_1") (pinfunction "GND_29_1") (pintype "power_in"))
      (node (ref "U2") (pin "29_2") (pinfunction "GND_29_2") (pintype "power_in"))
      (node (ref "U2") (pin "29_3") (pinfunction "GND_29_3") (pintype "power_in"))
      (node (ref "U2") (pin "29_4") (pinfunction "GND_29_4") (pintype "power_in"))
      (node (ref "U2") (pin "29_5") (pinfunction "GND_29_5") (pintype "power_in"))
      (node (ref "U2") (pin "29_6") (pinfunction "GND_29_6") (pintype "power_in"))
      (node (ref "U2") (pin "29_7") (pinfunction "GND_29_7") (pintype "power_in"))
      (node (ref "U2") (pin "29_8") (pinfunction "GND_29_8") (pintype "power_in"))
      (node (ref "U2") (pin "29_9") (pinfunction "GND_29_9") (pintype "power_in"))
      (node (ref "U3") (pin "13") (pinfunction "GND_13") (pintype "power_in"))
      (node (ref "U4") (pin "1") (pinfunction "CTG_1") (pintype "power_in"))
      (node (ref "U4") (pin "4") (pinfunction "GND_4") (pintype "power_in"))
      (node (ref "U4") (pin "6") (pinfunction "QSTRT_6") (pintype "input"))
      (node (ref "U4") (pin "9") (pinfunction "EP_9") (pintype "power_in"))
    )
    (net (code "14") (name "GPIO8") (class "Default")
      (node (ref "R1") (pin "1") (pinfunction "1_1") (pintype "passive"))
      (node (ref "U2") (pin "10") (pinfunction "IO8_10") (pintype "bidirectional"))
    )
    (net (code "15") (name "I2C_PW") (class "Default")
      (node (ref "C1") (pin "1") (pinfunction "1_1") (pintype "passive"))
      (node (ref "C2") (pin "1") (pinfunction "1_1") (pintype "passive"))
      (node (ref "R1_PINH") (pin "2") (pinfunction "2_2") (pintype "passive"))
      (node (ref "R2-PINH") (pin "2") (pinfunction "2_2") (pintype "passive"))
      (node (ref "SENSOR2") (pin "2") (pinfunction "CSB_2") (pintype "input"))
      (node (ref "SENSOR2") (pin "6") (pinfunction "VDDIO_6") (pintype "power_in"))
      (node (ref "SENSOR2") (pin "8") (pinfunction "VDD_8") (pintype "power_in"))
      (node (ref "U2") (pin "17") (pinfunction "IO19_17") (pintype "bidirectional"))
    )
    (net (code "16") (name "INT_RTC") (class "Default")
      (node (ref "R1_PINH1") (pin "1") (pinfunction "1_1") (pintype "passive"))
      (node (ref "TP15") (pin "TP") (pinfunction "TP_TP") (pintype "input"))
      (node (ref "U2") (pin "8") (pinfunction "IO0_8") (pintype "bidirectional"))
      (node (ref "U3") (pin "3") (pinfunction "SQW/~{INT}_3") (pintype "output"))
    )
    (net (code "17") (name "IO{slash}BOOT") (class "Default")
      (node (ref "BOOT_BUTTON") (pin "3") (pinfunction "3_3") (pintype "passive"))
      (node (ref "BOOT_BUTTON") (pin "4") (pinfunction "4_4") (pintype "passive"))
      (node (ref "C6") (pin "1") (pinfunction "1_1") (pintype "passive"))
      (node (ref "R_BOOT") (pin "1") (pinfunction "1_1") (pintype "passive"))
      (node (ref "U2") (pin "15") (pinfunction "IO9_15") (pintype "bidirectional"))
    )
    (net (code "18") (name "IO{slash}CHANGE") (class "Default")
      (node (ref "C10") (pin "1") (pinfunction "1_1") (pintype "passive"))
      (node (ref "CHANGE_BUTTON") (pin "3") (pinfunction "3_3") (pintype "passive"))
      (node (ref "CHANGE_BUTTON") (pin "4") (pinfunction "4_4") (pintype "passive"))
      (node (ref "R_CHANGE") (pin "1") (pinfunction "1_1") (pintype "passive"))
      (node (ref "U2") (pin "23") (pinfunction "IO15_23") (pintype "bidirectional"))
    )
    (net (code "19") (name "MISO") (class "Default")
      (node (ref "D12") (pin "2") (pinfunction "2_2") (pintype "passive"))
      (node (ref "J4") (pin "P7") (pinfunction "DAT0_P7") (pintype "bidirectional"))
      (node (ref "R8") (pin "1") (pinfunction "1_1") (pintype "passive"))
      (node (ref "TP6") (pin "TP") (pinfunction "TP_TP") (pintype "input"))
      (node (ref "U1") (pin "2") (pinfunction "DO(IO1)_2") (pintype "bidirectional"))
      (node (ref "U2") (pin "27") (pinfunction "IO2_27") (pintype "bidirectional"))
    )
    (net (code "20") (name "MOSI") (class "Default")
      (node (ref "D11") (pin "2") (pinfunction "2_2") (pintype "passive"))
      (node (ref "J1") (pin "14") (pinfunction "14_14") (pintype "bidirectional"))
      (node (ref "J4") (pin "P3") (pinfunction "CMD_P3") (pintype "bidirectional"))
      (node (ref "R7") (pin "1") (pinfunction "1_1") (pintype "passive"))
      (node (ref "TP7") (pin "TP") (pinfunction "TP_TP") (pintype "input"))
      (node (ref "U1") (pin "5") (pinfunction "DI(IO0)_5") (pintype "bidirectional"))
      (node (ref "U2") (pin "7") (pinfunction "IO7_7") (pintype "bidirectional"))
    )
    (net (code "21") (name "Net-(CHG_LED-PadC)") (class "Default")
      (node (ref "CHG_LED") (pin "C") (pinfunction "C_C") (pintype "passive"))
      (node (ref "R1_BAT") (pin "1") (pinfunction "1_1") (pintype "passive"))
    )
    (net (code "22") (name "Net-(D2-CATHODE)") (class "Default")
      (node (ref "C1_BAT1") (pin "1") (pinfunction "1_1") (pintype "passive"))
      (node (ref "D2") (pin "1") (pinfunction "CATHODE_1") (pintype "bidirectional"))
      (node (ref "IC1") (pin "1") (pinfunction "VIN_1") (pintype "bidirectional"))
      (node (ref "IC1") (pin "3") (pinfunction "CE_3") (pintype "bidirectional"))
      (node (ref "Q1") (pin "2") (pinfunction "S_2") (pintype "bidirectional"))
    )
    (net (code "23") (name "Net-(D3-A)") (class "Default")
      (node (ref "C4") (pin "1") (pinfunction "1_1") (pintype "passive"))
      (node (ref "D3") (pin "2") (pinfunction "A_2") (pintype "bidirectional"))
      (node (ref "D4") (pin "1") (pinfunction "K_1") (pintype "bidirectional"))
    )
    (net (code "24") (name "Net-(D7-CATHODE)") (class "Default")
      (node (ref "D7") (pin "1") (pinfunction "CATHODE_1") (pintype "bidirectional"))
      (node (ref "R_CAPACITOR") (pin "1") (pinfunction "1_1") (pintype "passive"))
    )
    (net (code "25") (name "Net-(EPD_C1-Pad2)") (class "Default")
      (node (ref "EPD_C1") (pin "2") (pinfunction "2_2") (pintype "passive"))
      (node (ref "J1") (pin "4") (pinfunction "4_4") (pintype "bidirectional"))
    )
    (net (code "26") (name "Net-(EPD_C2-Pad2)") (class "Default")
      (node (ref "EPD_C2") (pin "2") (pinfunction "2_2") (pintype "passive"))
      (node (ref "J1") (pin "5") (pinfunction "5_5") (pintype "bidirectional"))
    )
    (net (code "27") (name "Net-(EPD_C5-Pad2)") (class "Default")
      (node (ref "EPD_C5") (pin "2") (pinfunction "2_2") (pintype "passive"))
      (node (ref "J1") (pin "15") (pinfunction "15_15") (pintype "bidirectional"))
    )
    (net (code "28") (name "Net-(EPD_C6-Pad2)") (class "Default")
      (node (ref "EPD_C6") (pin "2") (pinfunction "2_2") (pintype "passive"))
      (node (ref "J1") (pin "18") (pinfunction "18_18") (pintype "bidirectional"))
    )
    (net (code "29") (name "Net-(EPD_C7-Pad2)") (class "Default")
      (node (ref "EPD_C7") (pin "2") (pinfunction "2_2") (pintype "passive"))
      (node (ref "J1") (pin "19") (pinfunction "19_19") (pintype "bidirectional"))
    )
    (net (code "30") (name "Net-(EPD_C8-Pad2)") (class "Default")
      (node (ref "EPD_C8") (pin "2") (pinfunction "2_2") (pintype "passive"))
      (node (ref "J1") (pin "20") (pinfunction "20_20") (pintype "bidirectional"))
    )
    (net (code "31") (name "Net-(EPD_C10-Pad2)") (class "Default")
      (node (ref "EPD_C10") (pin "2") (pinfunction "2_2") (pintype "passive"))
      (node (ref "J1") (pin "22") (pinfunction "22_22") (pintype "bidirectional"))
    )
    (net (code "32") (name "Net-(EPD_C12-Pad2)") (class "Default")
      (node (ref "EPD_C12") (pin "2") (pinfunction "2_2") (pintype "passive"))
      (node (ref "J1") (pin "24") (pinfunction "24_24") (pintype "bidirectional"))
    )
    (net (code "33") (name "Net-(IC5-CT)") (class "Default")
      (node (ref "C_DELAY") (pin "1") (pinfunction "1_1") (pintype "passive"))
      (node (ref "IC5") (pin "5") (pinfunction "CT_5") (pintype "bidirectional"))
    )
    (net (code "34") (name "Net-(J2-PadA5)") (class "Default")
      (node (ref "J2") (pin "A5") (pinfunction "A5_A5") (pintype "bidirectional"))
      (node (ref "R2-USB1") (pin "2") (pinfunction "2_2") (pintype "passive"))
    )
    (net (code "35") (name "Net-(J2-PadB5)") (class "Default")
      (node (ref "J2") (pin "B5") (pinfunction "B5_B5") (pintype "bidirectional"))
      (node (ref "R2-USB") (pin "1") (pinfunction "1_1") (pintype "passive"))
    )
    (net (code "36") (name "Net-(MCP73831-PROG)") (class "Default")
      (node (ref "MCP73831") (pin "5") (pinfunction "PROG_5") (pintype "input"))
      (node (ref "R2_BAT") (pin "2") (pinfunction "2_2") (pintype "passive"))
    )
    (net (code "37") (name "Net-(MCP73831-STAT)") (class "Default")
      (node (ref "MCP73831") (pin "1") (pinfunction "STAT_1") (pintype "output"))
      (node (ref "R1_BAT") (pin "2") (pinfunction "2_2") (pintype "passive"))
    )
    (net (code "38") (name "PREVGH") (class "Default")
      (node (ref "D5") (pin "1") (pinfunction "K_1") (pintype "bidirectional"))
      (node (ref "EPD_C9") (pin "2") (pinfunction "2_2") (pintype "passive"))
      (node (ref "J1") (pin "21") (pinfunction "21_21") (pintype "bidirectional"))
    )
    (net (code "39") (name "PREVGL") (class "Default")
      (node (ref "D4") (pin "2") (pinfunction "A_2") (pintype "bidirectional"))
      (node (ref "EPD_C11") (pin "2") (pinfunction "2_2") (pintype "passive"))
      (node (ref "J1") (pin "23") (pinfunction "23_23") (pintype "bidirectional"))
    )
    (net (code "40") (name "RESE") (class "Default")
      (node (ref "J1") (pin "3") (pinfunction "3_3") (pintype "bidirectional"))
      (node (ref "Q3") (pin "2") (pinfunction "S_2") (pintype "bidirectional"))
      (node (ref "R2") (pin "2") (pinfunction "2_2") (pintype "passive"))
      (node (ref "R3") (pin "2") (pinfunction "2_2") (pintype "passive"))
      (node (ref "SJ1") (pin "2") (pinfunction "2_2") (pintype "passive"))
    )
    (net (code "41") (name "RESE'") (class "Default")
      (node (ref "R3") (pin "1") (pinfunction "1_1") (pintype "passive"))
    )
    (net (code "42") (name "RESET") (class "Default")
      (node (ref "C5") (pin "1") (pinfunction "1_1") (pintype "passive"))
      (node (ref "IC5") (pin "1") (pinfunction "VOUT_1") (pintype "bidirectional"))
      (node (ref "RESET_BUTTON") (pin "3") (pinfunction "3_3") (pintype "passive"))
      (node (ref "RESET_BUTTON") (pin "4") (pinfunction "4_4") (pintype "passive"))
      (node (ref "R_RESET") (pin "1") (pinfunction "1_1") (pintype "passive"))
      (node (ref "U2") (pin "3") (pinfunction "EN_3") (pintype "input"))
    )
    (net (code "43") (name "RTC_RST") (class "Default")
      (node (ref "U2") (pin "16") (pinfunction "IO18_16") (pintype "bidirectional"))
      (node (ref "U3") (pin "4") (pinfunction "~{RST}_4") (pintype "input"))
    )
    (net (code "44") (name "RX") (class "Default")
      (node (ref "TP2") (pin "TP") (pinfunction "TP_TP") (pintype "input"))
      (node (ref "U2") (pin "24") (pinfunction "RXD0/GPIO17_24") (pintype "bidirectional"))
    )
    (net (code "45") (name "SCK") (class "Default")
      (node (ref "D10") (pin "2") (pinfunction "2_2") (pintype "passive"))
      (node (ref "J1") (pin "13") (pinfunction "13_13") (pintype "bidirectional"))
      (node (ref "J4") (pin "P5") (pinfunction "CLK_P5") (pintype "bidirectional"))
      (node (ref "R6") (pin "1") (pinfunction "1_1") (pintype "passive"))
      (node (ref "TP8") (pin "TP") (pinfunction "TP_TP") (pintype "input"))
      (node (ref "U1") (pin "6") (pinfunction "CLK_6") (pintype "input"))
      (node (ref "U2") (pin "6") (pinfunction "IO6_6") (pintype "bidirectional"))
    )
    (net (code "46") (name "SCL") (class "Default")
      (node (ref "J3") (pin "4") (pinfunction "4_4") (pintype "passive"))
      (node (ref "R2-PINH") (pin "1") (pinfunction "1_1") (pintype "passive"))
      (node (ref "SENSOR2") (pin "4") (pinfunction "SCK_4") (pintype "input"))
      (node (ref "U2") (pin "20") (pinfunction "IO22_20") (pintype "bidirectional"))
      (node (ref "U3") (pin "16") (pinfunction "SCL_16") (pintype "input"))
      (node (ref "U4") (pin "5") (pinfunction "~{ALERT}_5") (pintype "output"))
      (node (ref "U4") (pin "7") (pinfunction "SCL_7") (pintype "input"))
    )
    (net (code "47") (name "SDA") (class "Default")
      (node (ref "J3") (pin "3") (pinfunction "3_3") (pintype "passive"))
      (node (ref "R1_PINH") (pin "1") (pinfunction "1_1") (pintype "passive"))
      (node (ref "SENSOR2") (pin "3") (pinfunction "SDI_3") (pintype "bidirectional"))
      (node (ref "U2") (pin "19") (pinfunction "IO21_19") (pintype "bidirectional"))
      (node (ref "U3") (pin "15") (pinfunction "SDA_15") (pintype "bidirectional"))
      (node (ref "U4") (pin "8") (pinfunction "SDA_8") (pintype "bidirectional"))
    )
    (net (code "48") (name "SRC") (class "Default")
      (node (ref "C4") (pin "2") (pinfunction "2_2") (pintype "passive"))
      (node (ref "D5") (pin "2") (pinfunction "A_2") (pintype "bidirectional"))
      (node (ref "L1") (pin "1") (pinfunction "1_1") (pintype "passive"))
      (node (ref "Q3") (pin "3") (pinfunction "D_3") (pintype "bidirectional"))
    )
    (net (code "49") (name "SS_SD") (class "Default")
      (node (ref "D8") (pin "2") (pinfunction "2_2") (pintype "passive"))
      (node (ref "J4") (pin "P2") (pinfunction "CD/DAT3_P2") (pintype "bidirectional"))
      (node (ref "R10") (pin "1") (pinfunction "1_1") (pintype "passive"))
      (node (ref "U2") (pin "4") (pinfunction "IO4_4") (pintype "bidirectional"))
    )
    (net (code "50") (name "TX") (class "Default")
      (node (ref "TP1") (pin "TP") (pinfunction "TP_TP") (pintype "input"))
      (node (ref "U2") (pin "25") (pinfunction "TXD0/GPIO16_25") (pintype "bidirectional"))
    )
    (net (code "51") (name "USB_D+") (class "Default")
      (node (ref "D1") (pin "1") (pinfunction "I/O1_1_1") (pintype "bidirectional"))
      (node (ref "U2") (pin "14") (pinfunction "IO13_14") (pintype "bidirectional"))
    )
    (net (code "52") (name "USB_D-") (class "Default")
      (node (ref "D1") (pin "3") (pinfunction "I/O2_1_3") (pintype "bidirectional"))
      (node (ref "U2") (pin "13") (pinfunction "IO12_13") (pintype "bidirectional"))
    )
    (net (code "53") (name "VBAT") (class "Default")
      (node (ref "C2_BAT") (pin "1") (pinfunction "1_1") (pintype "passive"))
      (node (ref "MCP73831") (pin "3") (pinfunction "VBAT_3") (pintype "power_in"))
      (node (ref "Q1") (pin "3") (pinfunction "D_3") (pintype "bidirectional"))
      (node (ref "TP3") (pin "TP") (pinfunction "TP_TP") (pintype "input"))
      (node (ref "U4") (pin "2") (pinfunction "CELL_2") (pintype "power_in"))
      (node (ref "U4") (pin "3") (pinfunction "VDD_3") (pintype "power_in"))
    )
    (net (code "54") (name "VBUS") (class "Default")
      (node (ref "C1_BAT") (pin "1") (pinfunction "1_1") (pintype "passive"))
      (node (ref "C4_USB") (pin "1") (pinfunction "1_1") (pintype "passive"))
      (node (ref "C5_USB") (pin "1") (pinfunction "1_1") (pintype "passive"))
      (node (ref "CHG_LED") (pin "A") (pinfunction "A_A") (pintype "passive"))
      (node (ref "D1") (pin "5") (pinfunction "VBUS_5") (pintype "bidirectional"))
      (node (ref "D2") (pin "2") (pinfunction "ANODE_2") (pintype "bidirectional"))
      (node (ref "J2") (pin "B9") (pinfunction "B9_B9") (pintype "bidirectional"))
      (node (ref "MCP73831") (pin "4") (pinfunction "VIN_4") (pintype "power_in"))
      (node (ref "PFMF.050.1") (pin "2") (pinfunction "2_2") (pintype "passive"))
      (node (ref "Q1") (pin "1") (pinfunction "G_1") (pintype "bidirectional"))
      (node (ref "R1_PWUSB") (pin "2") (pinfunction "2_2") (pintype "passive"))
      (node (ref "TP14") (pin "TP") (pinfunction "TP_TP") (pintype "input"))
    )
    (net (code "55") (name "VRTC") (class "Default")
      (node (ref "C10_SUPERCAP") (pin "1") (pinfunction "1_1") (pintype "passive"))
      (node (ref "C8") (pin "1") (pinfunction "1_1") (pintype "passive"))
      (node (ref "R_CAPACITOR") (pin "2") (pinfunction "2_2") (pintype "passive"))
      (node (ref "U3") (pin "14") (pinfunction "VBAT_14") (pintype "power_in"))
    )
    (net (code "56") (name "VUSB") (class "Default")
      (node (ref "J2") (pin "A4") (pinfunction "A4_A4") (pintype "bidirectional"))
      (node (ref "J2") (pin "A9") (pinfunction "A9_A9") (pintype "bidirectional"))
      (node (ref "J2") (pin "B4") (pinfunction "B4_B4") (pintype "bidirectional"))
      (node (ref "PFMF.050.1") (pin "1") (pinfunction "1_1") (pintype "passive"))
    )
    (net (code "57") (name "unconnected-(IC1-NC-Pad4)") (class "Default")
      (node (ref "IC1") (pin "4") (pinfunction "NC_4") (pintype "no_connect"))
    )
    (net (code "58") (name "unconnected-(IC5-NC-Pad4)") (class "Default")
      (node (ref "IC5") (pin "4") (pinfunction "NC_4") (pintype "no_connect"))
    )
    (net (code "59") (name "unconnected-(J1-Pad1)") (class "Default")
      (node (ref "J1") (pin "1") (pinfunction "1_1") (pintype "bidirectional"))
    )
    (net (code "60") (name "unconnected-(J1-Pad6)") (class "Default")
      (node (ref "J1") (pin "6") (pinfunction "6_6") (pintype "bidirectional"))
    )
    (net (code "61") (name "unconnected-(J1-Pad7)") (class "Default")
      (node (ref "J1") (pin "7") (pinfunction "7_7") (pintype "bidirectional"))
    )
    (net (code "62") (name "unconnected-(J2-PadA8)") (class "Default")
      (node (ref "J2") (pin "A8") (pinfunction "A8_A8") (pintype "bidirectional"))
    )
    (net (code "63") (name "unconnected-(J2-PadB8)") (class "Default")
      (node (ref "J2") (pin "B8") (pinfunction "B8_B8") (pintype "bidirectional"))
    )
    (net (code "64") (name "unconnected-(J4-DAT1-PadP8)") (class "Default")
      (node (ref "J4") (pin "P8") (pinfunction "DAT1_P8") (pintype "bidirectional"))
    )
    (net (code "65") (name "unconnected-(J4-DAT2-PadP1)") (class "Default")
      (node (ref "J4") (pin "P1") (pinfunction "DAT2_P1") (pintype "bidirectional"))
    )
    (net (code "66") (name "unconnected-(J4-DETECTION_1-PadS1)") (class "Default")
      (node (ref "J4") (pin "S1") (pinfunction "DETECTION_1_S1") (pintype "bidirectional"))
    )
    (net (code "67") (name "unconnected-(J4-DETECTION_2-PadS2)") (class "Default")
      (node (ref "J4") (pin "S2") (pinfunction "DETECTION_2_S2") (pintype "bidirectional"))
    )
    (net (code "68") (name "unconnected-(U2-NC-Pad22)") (class "Default")
      (node (ref "U2") (pin "22") (pinfunction "NC_22") (pintype "no_connect"))
    )
  )
)
